# introAu.net
KiCad netlist of a schematic drawn in EAGLE
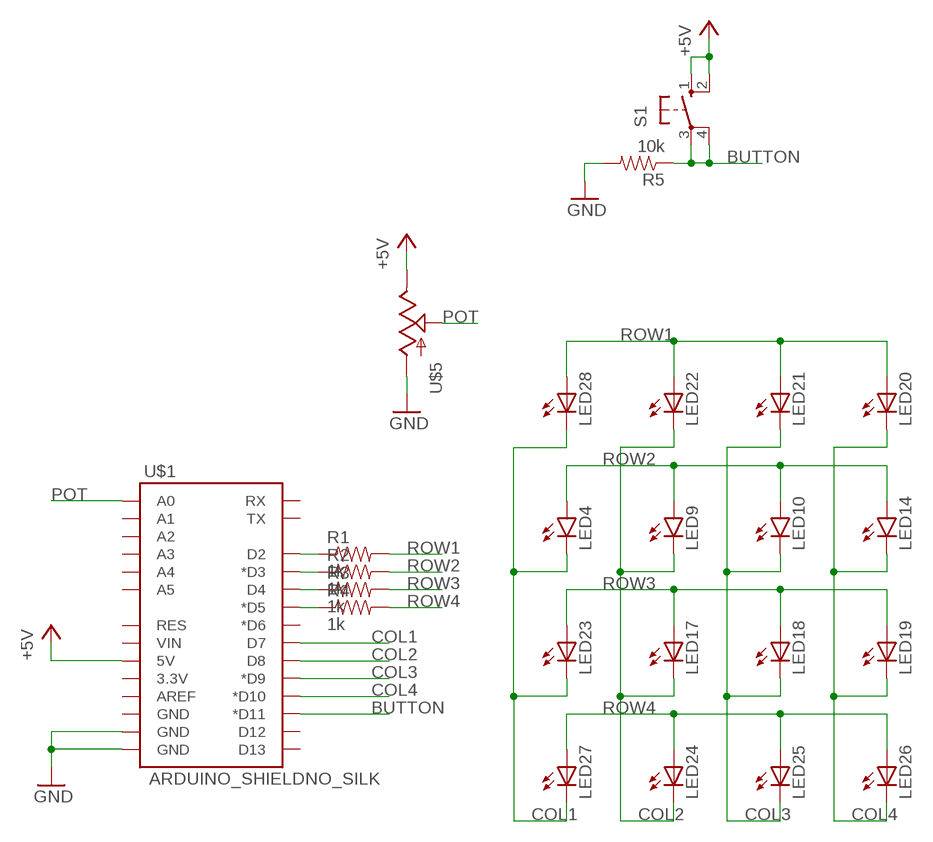
[diagram p0: schematic, sheet 1]

(export (version "E")
  (design (tool "Eeschema 10.0.6"))
  (components
    (comp (ref "LED4")
      (value "LED5MM")
      (footprint "eagle-import:LED5MM")
      (libsource (lib "eagle-import") (part "LED5MM"))
    )
    (comp (ref "LED9")
      (value "LED5MM")
      (footprint "eagle-import:LED5MM")
      (libsource (lib "eagle-import") (part "LED5MM"))
    )
    (comp (ref "LED10")
      (value "LED5MM")
      (footprint "eagle-import:LED5MM")
      (libsource (lib "eagle-import") (part "LED5MM"))
    )
    (comp (ref "LED14")
      (value "LED5MM")
      (footprint "eagle-import:LED5MM")
      (libsource (lib "eagle-import") (part "LED5MM"))
    )
    (comp (ref "LED17")
      (value "LEDCHIPLED_0805")
      (footprint "eagle-import:CHIPLED_0805")
      (libsource (lib "eagle-import") (part "LEDCHIPLED_0805"))
    )
    (comp (ref "LED18")
      (value "LEDCHIPLED_0805")
      (footprint "eagle-import:CHIPLED_0805")
      (libsource (lib "eagle-import") (part "LEDCHIPLED_0805"))
    )
    (comp (ref "LED19")
      (value "LEDCHIPLED_0805")
      (footprint "eagle-import:CHIPLED_0805")
      (libsource (lib "eagle-import") (part "LEDCHIPLED_0805"))
    )
    (comp (ref "LED20")
      (value "LEDCHIPLED_0805")
      (footprint "eagle-import:CHIPLED_0805")
      (libsource (lib "eagle-import") (part "LEDCHIPLED_0805"))
    )
    (comp (ref "LED21")
      (value "LEDCHIPLED_0805")
      (footprint "eagle-import:CHIPLED_0805")
      (libsource (lib "eagle-import") (part "LEDCHIPLED_0805"))
    )
    (comp (ref "LED22")
      (value "LEDCHIPLED_0805")
      (footprint "eagle-import:CHIPLED_0805")
      (libsource (lib "eagle-import") (part "LEDCHIPLED_0805"))
    )
    (comp (ref "LED23")
      (value "LEDCHIPLED_0805")
      (footprint "eagle-import:CHIPLED_0805")
      (libsource (lib "eagle-import") (part "LEDCHIPLED_0805"))
    )
    (comp (ref "LED24")
      (value "LEDCHIPLED_0805")
      (footprint "eagle-import:CHIPLED_0805")
      (libsource (lib "eagle-import") (part "LEDCHIPLED_0805"))
    )
    (comp (ref "LED25")
      (value "LEDCHIPLED_0805")
      (footprint "eagle-import:CHIPLED_0805")
      (libsource (lib "eagle-import") (part "LEDCHIPLED_0805"))
    )
    (comp (ref "LED26")
      (value "LEDCHIPLED_0805")
      (footprint "eagle-import:CHIPLED_0805")
      (libsource (lib "eagle-import") (part "LEDCHIPLED_0805"))
    )
    (comp (ref "LED27")
      (value "LEDCHIPLED_0805")
      (footprint "eagle-import:CHIPLED_0805")
      (libsource (lib "eagle-import") (part "LEDCHIPLED_0805"))
    )
    (comp (ref "LED28")
      (value "LEDCHIPLED_0805")
      (footprint "eagle-import:CHIPLED_0805")
      (libsource (lib "eagle-import") (part "LEDCHIPLED_0805"))
    )
    (comp (ref "R1")
      (value "1k")
      (footprint "eagle-import:AXIAL-0.3EZ")
      (libsource (lib "eagle-import") (part "1KOHM1/4W5%(PTH)HORIZ-KIT"))
    )
    (comp (ref "R2")
      (value "1k")
      (footprint "eagle-import:AXIAL-0.3EZ")
      (libsource (lib "eagle-import") (part "1KOHM1/4W5%(PTH)HORIZ-KIT"))
    )
    (comp (ref "R3")
      (value "1k")
      (footprint "eagle-import:AXIAL-0.3EZ")
      (libsource (lib "eagle-import") (part "1KOHM1/4W5%(PTH)HORIZ-KIT"))
    )
    (comp (ref "R4")
      (value "1k")
      (footprint "eagle-import:AXIAL-0.3EZ")
      (libsource (lib "eagle-import") (part "1KOHM1/4W5%(PTH)HORIZ-KIT"))
    )
    (comp (ref "R5")
      (value "10k")
      (footprint "eagle-import:AXIAL-0.3EZ")
      (libsource (lib "eagle-import") (part "1KOHM1/4W5%(PTH)HORIZ-KIT"))
    )
    (comp (ref "S1")
      (value "TACT_BUTTON")
      (footprint "eagle-import:B3F-10XX")
      (fields (field (name "MPN") "B3F-1000"))
      (libsource (lib "eagle-import") (part "TACT_BUTTON"))
    )
    (comp (ref "U$1")
      (value "ARDUINO_SHIELDNO_SILK")
      (footprint "eagle-import:DUEMILANOVE_VIAS")
      (libsource (lib "eagle-import") (part "ARDUINO_SHIELDNO_SILK"))
    )
    (comp (ref "U$5")
      (value "POT")
      (footprint "eagle-import:ALPS_POT")
      (libsource (lib "eagle-import") (part "POT"))
    )
  )
  (nets
    (net (code "1") (name "+5V") (class "Default")
      (node (ref "S1") (pin "1") (pinfunction "S_1") (pintype "passive"))
      (node (ref "S1") (pin "2") (pinfunction "S1_2") (pintype "passive"))
      (node (ref "U$1") (pin "5V") (pinfunction "5V_5V") (pintype "bidirectional"))
      (node (ref "U$5") (pin "P$1") (pinfunction "E_P$1") (pintype "passive"))
    )
    (net (code "2") (name "/BUTTON") (class "Default")
      (node (ref "R5") (pin "P$1") (pinfunction "1_P$1") (pintype "passive"))
      (node (ref "S1") (pin "3") (pinfunction "P_3") (pintype "passive"))
      (node (ref "S1") (pin "4") (pinfunction "P1_4") (pintype "passive"))
      (node (ref "U$1") (pin "D11") (pinfunction "*D11_D11") (pintype "bidirectional"))
    )
    (net (code "3") (name "/COL1") (class "Default")
      (node (ref "LED23") (pin "C") (pinfunction "C_C") (pintype "passive"))
      (node (ref "LED27") (pin "C") (pinfunction "C_C") (pintype "passive"))
      (node (ref "LED28") (pin "C") (pinfunction "C_C") (pintype "passive"))
      (node (ref "LED4") (pin "K") (pinfunction "C_K") (pintype "passive"))
      (node (ref "U$1") (pin "D7") (pinfunction "D7_D7") (pintype "bidirectional"))
    )
    (net (code "4") (name "/COL2") (class "Default")
      (node (ref "LED17") (pin "C") (pinfunction "C_C") (pintype "passive"))
      (node (ref "LED22") (pin "C") (pinfunction "C_C") (pintype "passive"))
      (node (ref "LED24") (pin "C") (pinfunction "C_C") (pintype "passive"))
      (node (ref "LED9") (pin "K") (pinfunction "C_K") (pintype "passive"))
      (node (ref "U$1") (pin "D8") (pinfunction "D8_D8") (pintype "bidirectional"))
    )
    (net (code "5") (name "/COL3") (class "Default")
      (node (ref "LED10") (pin "K") (pinfunction "C_K") (pintype "passive"))
      (node (ref "LED18") (pin "C") (pinfunction "C_C") (pintype "passive"))
      (node (ref "LED21") (pin "C") (pinfunction "C_C") (pintype "passive"))
      (node (ref "LED25") (pin "C") (pinfunction "C_C") (pintype "passive"))
      (node (ref "U$1") (pin "D9") (pinfunction "*D9_D9") (pintype "bidirectional"))
    )
    (net (code "6") (name "/COL4") (class "Default")
      (node (ref "LED14") (pin "K") (pinfunction "C_K") (pintype "passive"))
      (node (ref "LED19") (pin "C") (pinfunction "C_C") (pintype "passive"))
      (node (ref "LED20") (pin "C") (pinfunction "C_C") (pintype "passive"))
      (node (ref "LED26") (pin "C") (pinfunction "C_C") (pintype "passive"))
      (node (ref "U$1") (pin "D10") (pinfunction "*D10_D10") (pintype "bidirectional"))
    )
    (net (code "7") (name "/POT") (class "Default")
      (node (ref "U$1") (pin "A0") (pinfunction "A0_A0") (pintype "bidirectional"))
      (node (ref "U$5") (pin "P$2") (pinfunction "S_P$2") (pintype "passive"))
    )
    (net (code "8") (name "/ROW1") (class "Default")
      (node (ref "LED20") (pin "A") (pinfunction "A_A") (pintype "passive"))
      (node (ref "LED21") (pin "A") (pinfunction "A_A") (pintype "passive"))
      (node (ref "LED22") (pin "A") (pinfunction "A_A") (pintype "passive"))
      (node (ref "LED28") (pin "A") (pinfunction "A_A") (pintype "passive"))
      (node (ref "R1") (pin "P$2") (pinfunction "2_P$2") (pintype "passive"))
    )
    (net (code "9") (name "/ROW2") (class "Default")
      (node (ref "LED10") (pin "A") (pinfunction "A_A") (pintype "passive"))
      (node (ref "LED14") (pin "A") (pinfunction "A_A") (pintype "passive"))
      (node (ref "LED4") (pin "A") (pinfunction "A_A") (pintype "passive"))
      (node (ref "LED9") (pin "A") (pinfunction "A_A") (pintype "passive"))
      (node (ref "R2") (pin "P$2") (pinfunction "2_P$2") (pintype "passive"))
    )
    (net (code "10") (name "/ROW3") (class "Default")
      (node (ref "LED17") (pin "A") (pinfunction "A_A") (pintype "passive"))
      (node (ref "LED18") (pin "A") (pinfunction "A_A") (pintype "passive"))
      (node (ref "LED19") (pin "A") (pinfunction "A_A") (pintype "passive"))
      (node (ref "LED23") (pin "A") (pinfunction "A_A") (pintype "passive"))
      (node (ref "R3") (pin "P$2") (pinfunction "2_P$2") (pintype "passive"))
    )
    (net (code "11") (name "/ROW4") (class "Default")
      (node (ref "LED24") (pin "A") (pinfunction "A_A") (pintype "passive"))
      (node (ref "LED25") (pin "A") (pinfunction "A_A") (pintype "passive"))
      (node (ref "LED26") (pin "A") (pinfunction "A_A") (pintype "passive"))
      (node (ref "LED27") (pin "A") (pinfunction "A_A") (pintype "passive"))
      (node (ref "R4") (pin "P$2") (pinfunction "2_P$2") (pintype "passive"))
    )
    (net (code "12") (name "GND") (class "Default")
      (node (ref "R5") (pin "P$2") (pinfunction "2_P$2") (pintype "passive"))
      (node (ref "U$1") (pin "GND@0") (pinfunction "GND_GND@0") (pintype "bidirectional"))
      (node (ref "U$1") (pin "GND@1") (pinfunction "GND_GND@1") (pintype "bidirectional"))
      (node (ref "U$5") (pin "P$3") (pinfunction "A_P$3") (pintype "passive"))
    )
    (net (code "13") (name "Net-(R1-1)") (class "Default")
      (node (ref "R1") (pin "P$1") (pinfunction "1_P$1") (pintype "passive"))
      (node (ref "U$1") (pin "D2") (pinfunction "D2_D2") (pintype "bidirectional"))
    )
    (net (code "14") (name "Net-(R2-1)") (class "Default")
      (node (ref "R2") (pin "P$1") (pinfunction "1_P$1") (pintype "passive"))
      (node (ref "U$1") (pin "D3") (pinfunction "*D3_D3") (pintype "bidirectional"))
    )
    (net (code "15") (name "Net-(R3-1)") (class "Default")
      (node (ref "R3") (pin "P$1") (pinfunction "1_P$1") (pintype "passive"))
      (node (ref "U$1") (pin "D4") (pinfunction "D4_D4") (pintype "bidirectional"))
    )
    (net (code "16") (name "Net-(R4-1)") (class "Default")
      (node (ref "R4") (pin "P$1") (pinfunction "1_P$1") (pintype "passive"))
      (node (ref "U$1") (pin "D5") (pinfunction "*D5_D5") (pintype "bidirectional"))
    )
    (net (code "17") (name "unconnected-(U$1-*D6-PadD6)") (class "Default")
      (node (ref "U$1") (pin "D6") (pinfunction "*D6_D6") (pintype "bidirectional"))
    )
    (net (code "18") (name "unconnected-(U$1-GND-PadGND@2)") (class "Default")
      (node (ref "U$1") (pin "GND@2") (pinfunction "GND_GND@2") (pintype "bidirectional"))
    )
    (net (code "19") (name "unconnected-(U$1-Pad3.3V)") (class "Default")
      (node (ref "U$1") (pin "3.3V") (pinfunction "3.3V_3.3V") (pintype "bidirectional"))
    )
    (net (code "20") (name "unconnected-(U$1-PadA1)") (class "Default")
      (node (ref "U$1") (pin "A1") (pinfunction "A1_A1") (pintype "bidirectional"))
    )
    (net (code "21") (name "unconnected-(U$1-PadA2)") (class "Default")
      (node (ref "U$1") (pin "A2") (pinfunction "A2_A2") (pintype "bidirectional"))
    )
    (net (code "22") (name "unconnected-(U$1-PadA3)") (class "Default")
      (node (ref "U$1") (pin "A3") (pinfunction "A3_A3") (pintype "bidirectional"))
    )
    (net (code "23") (name "unconnected-(U$1-PadA4)") (class "Default")
      (node (ref "U$1") (pin "A4") (pinfunction "A4_A4") (pintype "bidirectional"))
    )
    (net (code "24") (name "unconnected-(U$1-PadA5)") (class "Default")
      (node (ref "U$1") (pin "A5") (pinfunction "A5_A5") (pintype "bidirectional"))
    )
    (net (code "25") (name "unconnected-(U$1-PadAREF)") (class "Default")
      (node (ref "U$1") (pin "AREF") (pinfunction "AREF_AREF") (pintype "bidirectional"))
    )
    (net (code "26") (name "unconnected-(U$1-PadD12)") (class "Default")
      (node (ref "U$1") (pin "D12") (pinfunction "D12_D12") (pintype "bidirectional"))
    )
    (net (code "27") (name "unconnected-(U$1-PadD13)") (class "Default")
      (node (ref "U$1") (pin "D13") (pinfunction "D13_D13") (pintype "bidirectional"))
    )
    (net (code "28") (name "unconnected-(U$1-PadRES)") (class "Default")
      (node (ref "U$1") (pin "RES") (pinfunction "RES_RES") (pintype "bidirectional"))
    )
    (net (code "29") (name "unconnected-(U$1-PadRX)") (class "Default")
      (node (ref "U$1") (pin "RX") (pinfunction "RX_RX") (pintype "bidirectional"))
    )
    (net (code "30") (name "unconnected-(U$1-PadTX)") (class "Default")
      (node (ref "U$1") (pin "TX") (pinfunction "TX_TX") (pintype "bidirectional"))
    )
    (net (code "31") (name "unconnected-(U$1-PadVIN)") (class "Default")
      (node (ref "U$1") (pin "VIN") (pinfunction "VIN_VIN") (pintype "bidirectional"))
    )
  )
)
